# PSU2.net
KiCad netlist of a schematic drawn in Altium Designer
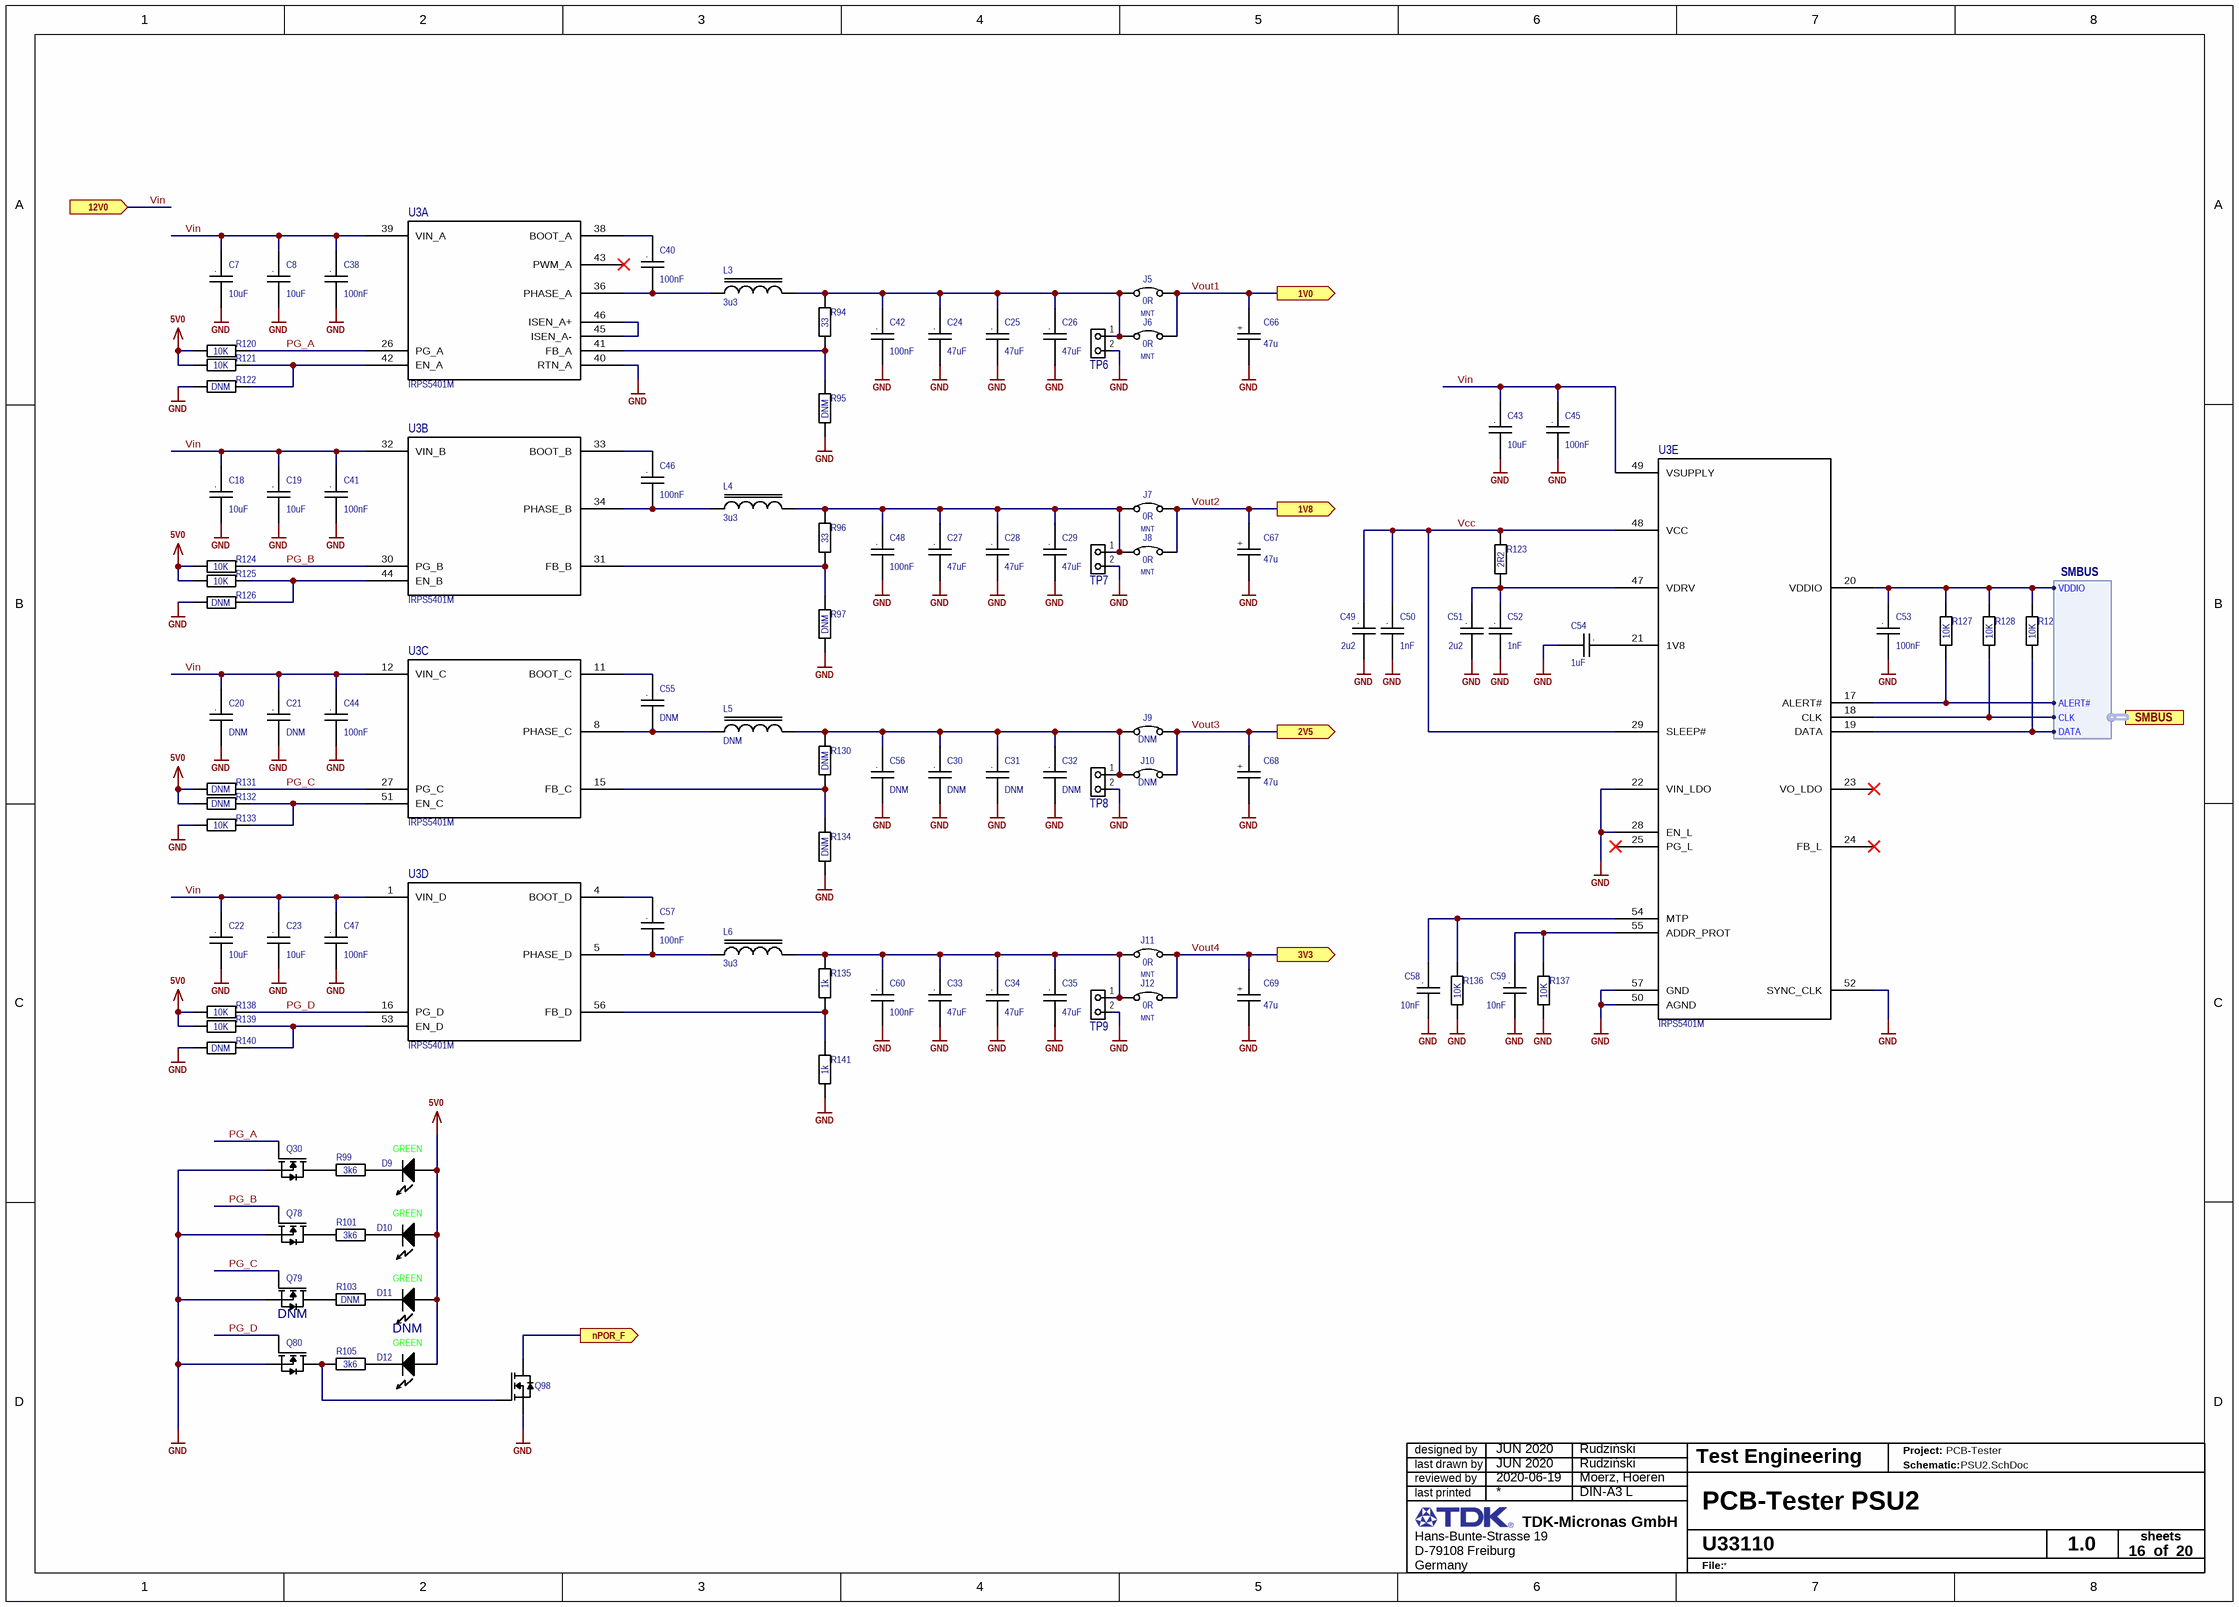
[diagram p0: PSU2.SchDoc]

(export (version "E")
  (design (tool "Eeschema 10.0.6"))
  (components
    (comp (ref "C7")
      (value "10uF")
      (footprint "C1206 Reflow")
      (description "CAP CER 10UF 25V X7R 1206")
      (fields
        (field (name "TOLERANCE") "±10%")
        (field (name "02. DISTRIBUTOR PART NUMBER") "445-7705-6-ND")
        (field (name "13. CREATED DATE/NAME") "AUG2018/Hören")
      )
      (libsource (lib "chickenfood") (part "C"))
    )
    (comp (ref "C8")
      (value "10uF")
      (footprint "C1206 Reflow")
      (description "CAP CER 10UF 25V X7R 1206")
      (fields
        (field (name "TOLERANCE") "±10%")
        (field (name "02. DISTRIBUTOR PART NUMBER") "445-7705-6-ND")
        (field (name "13. CREATED DATE/NAME") "AUG2018/Hören")
      )
      (libsource (lib "chickenfood") (part "C"))
    )
    (comp (ref "C18")
      (value "10uF")
      (footprint "C1206 Reflow")
      (description "CAP CER 10UF 25V X7R 1206")
      (fields
        (field (name "TOLERANCE") "±10%")
        (field (name "02. DISTRIBUTOR PART NUMBER") "445-7705-6-ND")
        (field (name "13. CREATED DATE/NAME") "AUG2018/Hören")
      )
      (libsource (lib "chickenfood") (part "C"))
    )
    (comp (ref "C19")
      (value "10uF")
      (footprint "C1206 Reflow")
      (description "CAP CER 10UF 25V X7R 1206")
      (fields
        (field (name "TOLERANCE") "±10%")
        (field (name "02. DISTRIBUTOR PART NUMBER") "445-7705-6-ND")
        (field (name "13. CREATED DATE/NAME") "AUG2018/Hören")
      )
      (libsource (lib "chickenfood") (part "C"))
    )
    (comp (ref "C20")
      (value "DNM")
      (footprint "C1206 Reflow")
      (description "CAP CER 10UF 25V X7R 1206")
      (fields
        (field (name "TOLERANCE") "±10%")
        (field (name "02. DISTRIBUTOR PART NUMBER") "445-7705-6-ND")
        (field (name "13. CREATED DATE/NAME") "AUG2018/Hören")
      )
      (libsource (lib "chickenfood") (part "C"))
    )
    (comp (ref "C21")
      (value "DNM")
      (footprint "C1206 Reflow")
      (description "CAP CER 10UF 25V X7R 1206")
      (fields
        (field (name "TOLERANCE") "±10%")
        (field (name "02. DISTRIBUTOR PART NUMBER") "445-7705-6-ND")
        (field (name "13. CREATED DATE/NAME") "AUG2018/Hören")
      )
      (libsource (lib "chickenfood") (part "C"))
    )
    (comp (ref "C22")
      (value "10uF")
      (footprint "C1206 Reflow")
      (description "CAP CER 10UF 25V X7R 1206")
      (fields
        (field (name "TOLERANCE") "±10%")
        (field (name "02. DISTRIBUTOR PART NUMBER") "445-7705-6-ND")
        (field (name "13. CREATED DATE/NAME") "AUG2018/Hören")
      )
      (libsource (lib "chickenfood") (part "C"))
    )
    (comp (ref "C23")
      (value "10uF")
      (footprint "C1206 Reflow")
      (description "CAP CER 10UF 25V X7R 1206")
      (fields
        (field (name "TOLERANCE") "±10%")
        (field (name "02. DISTRIBUTOR PART NUMBER") "445-7705-6-ND")
        (field (name "13. CREATED DATE/NAME") "AUG2018/Hören")
      )
      (libsource (lib "chickenfood") (part "C"))
    )
    (comp (ref "C24")
      (value "47uF")
      (footprint "C1210 Reflow")
      (description "CAP CER 47UF 10V X5R 1210")
      (fields
        (field (name "TOLERANCE") "±20%")
        (field (name "02. DISTRIBUTOR PART NUMBER") "1276-3380-6-ND")
        (field (name "13. CREATED DATE/NAME") "AUG2018/Hören")
      )
      (libsource (lib "chickenfood") (part "C"))
    )
    (comp (ref "C25")
      (value "47uF")
      (footprint "C1210 Reflow")
      (description "CAP CER 47UF 10V X5R 1210")
      (fields
        (field (name "TOLERANCE") "±20%")
        (field (name "02. DISTRIBUTOR PART NUMBER") "1276-3380-6-ND")
        (field (name "13. CREATED DATE/NAME") "AUG2018/Hören")
      )
      (libsource (lib "chickenfood") (part "C"))
    )
    (comp (ref "C26")
      (value "47uF")
      (footprint "C1210 Reflow")
      (description "CAP CER 47UF 10V X5R 1210")
      (fields
        (field (name "TOLERANCE") "±20%")
        (field (name "02. DISTRIBUTOR PART NUMBER") "1276-3380-6-ND")
        (field (name "13. CREATED DATE/NAME") "AUG2018/Hören")
      )
      (libsource (lib "chickenfood") (part "C"))
    )
    (comp (ref "C27")
      (value "47uF")
      (footprint "C1210 Reflow")
      (description "CAP CER 47UF 10V X5R 1210")
      (fields
        (field (name "TOLERANCE") "±20%")
        (field (name "02. DISTRIBUTOR PART NUMBER") "1276-3380-6-ND")
        (field (name "13. CREATED DATE/NAME") "AUG2018/Hören")
      )
      (libsource (lib "chickenfood") (part "C"))
    )
    (comp (ref "C28")
      (value "47uF")
      (footprint "C1210 Reflow")
      (description "CAP CER 47UF 10V X5R 1210")
      (fields
        (field (name "TOLERANCE") "±20%")
        (field (name "02. DISTRIBUTOR PART NUMBER") "1276-3380-6-ND")
        (field (name "13. CREATED DATE/NAME") "AUG2018/Hören")
      )
      (libsource (lib "chickenfood") (part "C"))
    )
    (comp (ref "C29")
      (value "47uF")
      (footprint "C1210 Reflow")
      (description "CAP CER 47UF 10V X5R 1210")
      (fields
        (field (name "TOLERANCE") "±20%")
        (field (name "02. DISTRIBUTOR PART NUMBER") "1276-3380-6-ND")
        (field (name "13. CREATED DATE/NAME") "AUG2018/Hören")
      )
      (libsource (lib "chickenfood") (part "C"))
    )
    (comp (ref "C30")
      (value "DNM")
      (footprint "C1210 Reflow")
      (description "CAP CER 47UF 10V X5R 1210")
      (fields
        (field (name "TOLERANCE") "±20%")
        (field (name "02. DISTRIBUTOR PART NUMBER") "1276-3380-6-ND")
        (field (name "13. CREATED DATE/NAME") "AUG2018/Hören")
      )
      (libsource (lib "chickenfood") (part "C"))
    )
    (comp (ref "C31")
      (value "DNM")
      (footprint "C1210 Reflow")
      (description "CAP CER 47UF 10V X5R 1210")
      (fields
        (field (name "TOLERANCE") "±20%")
        (field (name "02. DISTRIBUTOR PART NUMBER") "1276-3380-6-ND")
        (field (name "13. CREATED DATE/NAME") "AUG2018/Hören")
      )
      (libsource (lib "chickenfood") (part "C"))
    )
    (comp (ref "C32")
      (value "DNM")
      (footprint "C1210 Reflow")
      (description "CAP CER 47UF 10V X5R 1210")
      (fields
        (field (name "TOLERANCE") "±20%")
        (field (name "02. DISTRIBUTOR PART NUMBER") "1276-3380-6-ND")
        (field (name "13. CREATED DATE/NAME") "AUG2018/Hören")
      )
      (libsource (lib "chickenfood") (part "C"))
    )
    (comp (ref "C33")
      (value "47uF")
      (footprint "C1210 Reflow")
      (description "CAP CER 47UF 10V X5R 1210")
      (fields
        (field (name "TOLERANCE") "±20%")
        (field (name "02. DISTRIBUTOR PART NUMBER") "1276-3380-6-ND")
        (field (name "13. CREATED DATE/NAME") "AUG2018/Hören")
      )
      (libsource (lib "chickenfood") (part "C"))
    )
    (comp (ref "C34")
      (value "47uF")
      (footprint "C1210 Reflow")
      (description "CAP CER 47UF 10V X5R 1210")
      (fields
        (field (name "TOLERANCE") "±20%")
        (field (name "02. DISTRIBUTOR PART NUMBER") "1276-3380-6-ND")
        (field (name "13. CREATED DATE/NAME") "AUG2018/Hören")
      )
      (libsource (lib "chickenfood") (part "C"))
    )
    (comp (ref "C35")
      (value "47uF")
      (footprint "C1210 Reflow")
      (description "CAP CER 47UF 10V X5R 1210")
      (fields
        (field (name "TOLERANCE") "±20%")
        (field (name "02. DISTRIBUTOR PART NUMBER") "1276-3380-6-ND")
        (field (name "13. CREATED DATE/NAME") "AUG2018/Hören")
      )
      (libsource (lib "chickenfood") (part "C"))
    )
    (comp (ref "C38")
      (value "100nF")
      (footprint "C0402 Reflow")
      (description "CAP CER 0.1UF 25V X7R 0402")
      (fields
        (field (name "TOLERANCE") "±10%")
        (field (name "02. DISTRIBUTOR PART NUMBER") "311-2077-6-ND")
        (field (name "13. CREATED DATE/NAME") "AUG2018/Hören")
      )
      (libsource (lib "chickenfood") (part "C"))
    )
    (comp (ref "C40")
      (value "100nF")
      (footprint "C0402 Reflow")
      (description "CAP CER 0.1UF 25V X7R 0402")
      (fields
        (field (name "TOLERANCE") "±10%")
        (field (name "02. DISTRIBUTOR PART NUMBER") "311-2077-6-ND")
        (field (name "13. CREATED DATE/NAME") "AUG2018/Hören")
      )
      (libsource (lib "chickenfood") (part "C"))
    )
    (comp (ref "C41")
      (value "100nF")
      (footprint "C0402 Reflow")
      (description "CAP CER 0.1UF 25V X7R 0402")
      (fields
        (field (name "TOLERANCE") "±10%")
        (field (name "02. DISTRIBUTOR PART NUMBER") "311-2077-6-ND")
        (field (name "13. CREATED DATE/NAME") "AUG2018/Hören")
      )
      (libsource (lib "chickenfood") (part "C"))
    )
    (comp (ref "C42")
      (value "100nF")
      (footprint "C0402 Reflow")
      (description "CAP CER 0.1UF 25V X7R 0402")
      (fields
        (field (name "TOLERANCE") "±10%")
        (field (name "02. DISTRIBUTOR PART NUMBER") "311-2077-6-ND")
        (field (name "13. CREATED DATE/NAME") "AUG2018/Hören")
      )
      (libsource (lib "chickenfood") (part "C"))
    )
    (comp (ref "C43")
      (value "10uF")
      (footprint "C1206 Reflow")
      (description "CAP CER 10UF 25V X7R 1206")
      (fields
        (field (name "TOLERANCE") "±10%")
        (field (name "02. DISTRIBUTOR PART NUMBER") "445-7705-6-ND")
        (field (name "13. CREATED DATE/NAME") "AUG2018/Hören")
      )
      (libsource (lib "chickenfood") (part "C"))
    )
    (comp (ref "C44")
      (value "100nF")
      (footprint "C0402 Reflow")
      (description "CAP CER 0.1UF 25V X7R 0402")
      (fields
        (field (name "TOLERANCE") "±10%")
        (field (name "02. DISTRIBUTOR PART NUMBER") "311-2077-6-ND")
        (field (name "13. CREATED DATE/NAME") "AUG2018/Hören")
      )
      (libsource (lib "chickenfood") (part "C"))
    )
    (comp (ref "C45")
      (value "100nF")
      (footprint "C0402 Reflow")
      (description "CAP CER 0.1UF 25V X7R 0402")
      (fields
        (field (name "TOLERANCE") "±10%")
        (field (name "02. DISTRIBUTOR PART NUMBER") "311-2077-6-ND")
        (field (name "13. CREATED DATE/NAME") "AUG2018/Hören")
      )
      (libsource (lib "chickenfood") (part "C"))
    )
    (comp (ref "C46")
      (value "100nF")
      (footprint "C0402 Reflow")
      (description "CAP CER 0.1UF 25V X7R 0402")
      (fields
        (field (name "TOLERANCE") "±10%")
        (field (name "02. DISTRIBUTOR PART NUMBER") "311-2077-6-ND")
        (field (name "13. CREATED DATE/NAME") "AUG2018/Hören")
      )
      (libsource (lib "chickenfood") (part "C"))
    )
    (comp (ref "C47")
      (value "100nF")
      (footprint "C0402 Reflow")
      (description "CAP CER 0.1UF 25V X7R 0402")
      (fields
        (field (name "TOLERANCE") "±10%")
        (field (name "02. DISTRIBUTOR PART NUMBER") "311-2077-6-ND")
        (field (name "13. CREATED DATE/NAME") "AUG2018/Hören")
      )
      (libsource (lib "chickenfood") (part "C"))
    )
    (comp (ref "C48")
      (value "100nF")
      (footprint "C0402 Reflow")
      (description "CAP CER 0.1UF 25V X7R 0402")
      (fields
        (field (name "TOLERANCE") "±10%")
        (field (name "02. DISTRIBUTOR PART NUMBER") "311-2077-6-ND")
        (field (name "13. CREATED DATE/NAME") "AUG2018/Hören")
      )
      (libsource (lib "chickenfood") (part "C"))
    )
    (comp (ref "C49")
      (value "2u2")
      (footprint "C0805 Reflow")
      (description "CAP CER 2.2UF 10V X7R 0805")
      (fields
        (field (name "02. DISTRIBUTOR PART NUMBER") "1276-1188-1-ND")
        (field (name "07. MANUFACTURER  PART NUMBER") "CL21B225KPFNNNE")
      )
      (libsource (lib "PCB-Tester-Board-V1") (part "C_11"))
    )
    (comp (ref "C50")
      (value "1nF")
      (footprint "C0402 Reflow")
      (description "CAP CER 1000PF 25V X7R 0402")
      (fields
        (field (name "TOLERANCE") "±10%")
        (field (name "02. DISTRIBUTOR PART NUMBER") "399-1031-6-ND")
        (field (name "13. CREATED DATE/NAME") "AUG2018/Hören")
      )
      (libsource (lib "PCB-Tester-Board-V1") (part "C_7"))
    )
    (comp (ref "C51")
      (value "2u2")
      (footprint "C0805 Reflow")
      (description "CAP CER 2.2UF 10V X7R 0805")
      (fields
        (field (name "02. DISTRIBUTOR PART NUMBER") "1276-1188-1-ND")
        (field (name "07. MANUFACTURER  PART NUMBER") "CL21B225KPFNNNE")
      )
      (libsource (lib "PCB-Tester-Board-V1") (part "C_11"))
    )
    (comp (ref "C52")
      (value "1nF")
      (footprint "C0402 Reflow")
      (description "CAP CER 1000PF 25V X7R 0402")
      (fields
        (field (name "TOLERANCE") "±10%")
        (field (name "02. DISTRIBUTOR PART NUMBER") "399-1031-6-ND")
        (field (name "13. CREATED DATE/NAME") "AUG2018/Hören")
      )
      (libsource (lib "PCB-Tester-Board-V1") (part "C_7"))
    )
    (comp (ref "C53")
      (value "100nF")
      (footprint "C0402 Reflow")
      (description "CAP CER 0.1UF 25V X7R 0402")
      (fields
        (field (name "TOLERANCE") "±10%")
        (field (name "02. DISTRIBUTOR PART NUMBER") "311-2077-6-ND")
        (field (name "13. CREATED DATE/NAME") "AUG2018/Hören")
      )
      (libsource (lib "chickenfood") (part "C"))
    )
    (comp (ref "C54")
      (value "1uF")
      (footprint "C0402 Reflow")
      (description "CAP CER 1UF 6.3V X7R 0402")
      (fields
        (field (name "TOLERANCE") "±10%")
        (field (name "02. DISTRIBUTOR PART NUMBER") "490-13339-6-ND")
        (field (name "13. CREATED DATE/NAME") "AUG2018/Hören")
      )
      (libsource (lib "PCB-Tester-Board-V1") (part "C_2"))
    )
    (comp (ref "C55")
      (value "DNM")
      (footprint "C0402 Reflow")
      (description "CAP CER 0.1UF 25V X7R 0402")
      (fields
        (field (name "TOLERANCE") "±10%")
        (field (name "02. DISTRIBUTOR PART NUMBER") "311-2077-6-ND")
        (field (name "13. CREATED DATE/NAME") "AUG2018/Hören")
      )
      (libsource (lib "chickenfood") (part "C"))
    )
    (comp (ref "C56")
      (value "DNM")
      (footprint "C0402 Reflow")
      (description "CAP CER 0.1UF 25V X7R 0402")
      (fields
        (field (name "TOLERANCE") "±10%")
        (field (name "02. DISTRIBUTOR PART NUMBER") "311-2077-6-ND")
        (field (name "13. CREATED DATE/NAME") "AUG2018/Hören")
      )
      (libsource (lib "chickenfood") (part "C"))
    )
    (comp (ref "C57")
      (value "100nF")
      (footprint "C0402 Reflow")
      (description "CAP CER 0.1UF 25V X7R 0402")
      (fields
        (field (name "TOLERANCE") "±10%")
        (field (name "02. DISTRIBUTOR PART NUMBER") "311-2077-6-ND")
        (field (name "13. CREATED DATE/NAME") "AUG2018/Hören")
      )
      (libsource (lib "chickenfood") (part "C"))
    )
    (comp (ref "C58")
      (value "10nF")
      (footprint "C0402 Reflow")
      (description "CAP CER 0.01UF 25V X7R 0402")
      (fields (field (name "TOLERANCE") "±10%") (field (name "02. DISTRIBUTOR PART NUMBER") "490-6043-1-ND"))
      (libsource (lib "PCB-Tester-Board-V1") (part "C_10"))
    )
    (comp (ref "C59")
      (value "10nF")
      (footprint "C0402 Reflow")
      (description "CAP CER 0.01UF 25V X7R 0402")
      (fields (field (name "TOLERANCE") "±10%") (field (name "02. DISTRIBUTOR PART NUMBER") "490-6043-1-ND"))
      (libsource (lib "PCB-Tester-Board-V1") (part "C_10"))
    )
    (comp (ref "C60")
      (value "100nF")
      (footprint "C0402 Reflow")
      (description "CAP CER 0.1UF 25V X7R 0402")
      (fields
        (field (name "TOLERANCE") "±10%")
        (field (name "02. DISTRIBUTOR PART NUMBER") "311-2077-6-ND")
        (field (name "13. CREATED DATE/NAME") "AUG2018/Hören")
      )
      (libsource (lib "chickenfood") (part "C"))
    )
    (comp (ref "C66")
      (value "47u")
      (footprint "CAP_TAN_B")
      (description "CAP TANT 47UF 20% 10V 1411")
      (fields
        (field (name "02. DISTRIBUTOR PART NUMBER") "478-12531-1-ND")
        (field (name "07. MANUFACTURER  PART NUMBER") "F971A476MBAHT3")
      )
      (libsource (lib "PCB-Tester-Board-V1") (part "C+_TAN"))
    )
    (comp (ref "C67")
      (value "47u")
      (footprint "CAP_TAN_B")
      (description "CAP TANT 47UF 20% 10V 1411")
      (fields
        (field (name "02. DISTRIBUTOR PART NUMBER") "478-12531-1-ND")
        (field (name "07. MANUFACTURER  PART NUMBER") "F971A476MBAHT3")
      )
      (libsource (lib "PCB-Tester-Board-V1") (part "C+_TAN"))
    )
    (comp (ref "C68")
      (value "47u")
      (footprint "CAP_TAN_B")
      (description "CAP TANT 47UF 20% 10V 1411")
      (fields
        (field (name "02. DISTRIBUTOR PART NUMBER") "478-12531-1-ND")
        (field (name "07. MANUFACTURER  PART NUMBER") "F971A476MBAHT3")
      )
      (libsource (lib "PCB-Tester-Board-V1") (part "C+_TAN"))
    )
    (comp (ref "C69")
      (value "47u")
      (footprint "CAP_TAN_B")
      (description "CAP TANT 47UF 20% 10V 1411")
      (fields
        (field (name "02. DISTRIBUTOR PART NUMBER") "478-12531-1-ND")
        (field (name "07. MANUFACTURER  PART NUMBER") "F971A476MBAHT3")
      )
      (libsource (lib "PCB-Tester-Board-V1") (part "C+_TAN"))
    )
    (comp (ref "D9")
      (value "D")
      (footprint "L0603G")
      (description "LED GREEN DIFFUSED 0603 SMD")
      (fields
        (field (name "02. DISTRIBUTOR PART NUMBER") "475-2709-6-ND")
        (field (name "07. MANUFACTURER  PART NUMBER") "LG L29K-G2J1-24-Z")
        (field (name "COLOR") "GREEN")
        (field (name "13. CREATED DATE/NAME") "AUG2018/Hören")
      )
      (libsource (lib "chickenfood") (part "LED"))
    )
    (comp (ref "D10")
      (value "D")
      (footprint "L0603G")
      (description "LED GREEN DIFFUSED 0603 SMD")
      (fields
        (field (name "02. DISTRIBUTOR PART NUMBER") "475-2709-6-ND")
        (field (name "07. MANUFACTURER  PART NUMBER") "LG L29K-G2J1-24-Z")
        (field (name "COLOR") "GREEN")
        (field (name "13. CREATED DATE/NAME") "AUG2018/Hören")
      )
      (libsource (lib "chickenfood") (part "LED"))
    )
    (comp (ref "D11")
      (value "D")
      (footprint "L0603G")
      (description "LED GREEN DIFFUSED 0603 SMD")
      (fields
        (field (name "02. DISTRIBUTOR PART NUMBER") "475-2709-6-ND")
        (field (name "07. MANUFACTURER  PART NUMBER") "LG L29K-G2J1-24-Z")
        (field (name "COLOR") "GREEN")
        (field (name "NICNAME") "DNM")
        (field (name "13. CREATED DATE/NAME") "AUG2018/Hören")
      )
      (libsource (lib "chickenfood") (part "LED"))
    )
    (comp (ref "D12")
      (value "D")
      (footprint "L0603G")
      (description "LED GREEN DIFFUSED 0603 SMD")
      (fields
        (field (name "02. DISTRIBUTOR PART NUMBER") "475-2709-6-ND")
        (field (name "07. MANUFACTURER  PART NUMBER") "LG L29K-G2J1-24-Z")
        (field (name "COLOR") "GREEN")
        (field (name "13. CREATED DATE/NAME") "AUG2018/Hören")
      )
      (libsource (lib "chickenfood") (part "LED"))
    )
    (comp (ref "J5")
      (value "0R")
      (footprint "JumperSMD")
      (description "RES SMD 0 OHM JUMPER 1/10W 0603")
      (fields
        (field (name "02. DISTRIBUTOR PART NUMBER") "311-0.0GRDKR-ND")
        (field (name "07. MANUFACTURER  PART NUMBER") "RC0603JR-070RL")
        (field (name "POPULATED") "MNT")
      )
      (libsource (lib "chickenfood") (part "Jumper SMD"))
    )
    (comp (ref "J6")
      (value "0R")
      (footprint "JumperSMD")
      (description "RES SMD 0 OHM JUMPER 1/10W 0603")
      (fields
        (field (name "02. DISTRIBUTOR PART NUMBER") "311-0.0GRDKR-ND")
        (field (name "07. MANUFACTURER  PART NUMBER") "RC0603JR-070RL")
        (field (name "POPULATED") "MNT")
      )
      (libsource (lib "chickenfood") (part "Jumper SMD"))
    )
    (comp (ref "J7")
      (value "0R")
      (footprint "JumperSMD")
      (description "RES SMD 0 OHM JUMPER 1/10W 0603")
      (fields
        (field (name "02. DISTRIBUTOR PART NUMBER") "311-0.0GRDKR-ND")
        (field (name "07. MANUFACTURER  PART NUMBER") "RC0603JR-070RL")
        (field (name "POPULATED") "MNT")
      )
      (libsource (lib "chickenfood") (part "Jumper SMD"))
    )
    (comp (ref "J8")
      (value "0R")
      (footprint "JumperSMD")
      (description "RES SMD 0 OHM JUMPER 1/10W 0603")
      (fields
        (field (name "02. DISTRIBUTOR PART NUMBER") "311-0.0GRDKR-ND")
        (field (name "07. MANUFACTURER  PART NUMBER") "RC0603JR-070RL")
        (field (name "POPULATED") "MNT")
      )
      (libsource (lib "chickenfood") (part "Jumper SMD"))
    )
    (comp (ref "J9")
      (value "DNM")
      (footprint "JumperSMD")
      (description "RES SMD 0 OHM JUMPER 1/10W 0603")
      (fields
        (field (name "02. DISTRIBUTOR PART NUMBER") "311-0.0GRDKR-ND")
        (field (name "07. MANUFACTURER  PART NUMBER") "RC0603JR-070RL")
      )
      (libsource (lib "chickenfood") (part "Jumper SMD"))
    )
    (comp (ref "J10")
      (value "DNM")
      (footprint "JumperSMD")
      (description "RES SMD 0 OHM JUMPER 1/10W 0603")
      (fields
        (field (name "02. DISTRIBUTOR PART NUMBER") "311-0.0GRDKR-ND")
        (field (name "07. MANUFACTURER  PART NUMBER") "RC0603JR-070RL")
      )
      (libsource (lib "chickenfood") (part "Jumper SMD"))
    )
    (comp (ref "J11")
      (value "0R")
      (footprint "JumperSMD")
      (description "RES SMD 0 OHM JUMPER 1/10W 0603")
      (fields
        (field (name "02. DISTRIBUTOR PART NUMBER") "311-0.0GRDKR-ND")
        (field (name "07. MANUFACTURER  PART NUMBER") "RC0603JR-070RL")
        (field (name "POPULATED") "MNT")
      )
      (libsource (lib "chickenfood") (part "Jumper SMD"))
    )
    (comp (ref "J12")
      (value "0R")
      (footprint "JumperSMD")
      (description "RES SMD 0 OHM JUMPER 1/10W 0603")
      (fields
        (field (name "02. DISTRIBUTOR PART NUMBER") "311-0.0GRDKR-ND")
        (field (name "07. MANUFACTURER  PART NUMBER") "RC0603JR-070RL")
        (field (name "POPULATED") "MNT")
      )
      (libsource (lib "chickenfood") (part "Jumper SMD"))
    )
    (comp (ref "L3")
      (value "L")
      (footprint "XAL7070")
      (description "Fixed Inductors 3.3uH Shld 20% 15.1A 9.42mOhms AECQ2")
      (fields
        (field (name "02. DISTRIBUTOR PART NUMBER") "994-XAL7070-332MEC")
        (field (name "07. MANUFACTURER  PART NUMBER") "XAL7070-332MEC")
        (field (name "INDUCTANCE") "3u3")
      )
      (libsource (lib "PCB-Tester-Board-V1") (part "INDUCTOR"))
    )
    (comp (ref "L4")
      (value "L")
      (footprint "XAL7070")
      (description "Fixed Inductors 3.3uH Shld 20% 15.1A 9.42mOhms AECQ2")
      (fields
        (field (name "02. DISTRIBUTOR PART NUMBER") "994-XAL7070-332MEC")
        (field (name "07. MANUFACTURER  PART NUMBER") "XAL7070-332MEC")
        (field (name "INDUCTANCE") "3u3")
      )
      (libsource (lib "PCB-Tester-Board-V1") (part "INDUCTOR"))
    )
    (comp (ref "L5")
      (value "L")
      (footprint "XAL7070")
      (description "Fixed Inductors 3.3uH Shld 20% 15.1A 9.42mOhms AECQ2")
      (fields
        (field (name "02. DISTRIBUTOR PART NUMBER") "994-XAL7070-332MEC")
        (field (name "07. MANUFACTURER  PART NUMBER") "XAL7070-332MEC")
        (field (name "INDUCTANCE") "DNM")
      )
      (libsource (lib "PCB-Tester-Board-V1") (part "INDUCTOR"))
    )
    (comp (ref "L6")
      (value "L")
      (footprint "XAL7070")
      (description "Fixed Inductors 3.3uH Shld 20% 15.1A 9.42mOhms AECQ2")
      (fields
        (field (name "02. DISTRIBUTOR PART NUMBER") "994-XAL7070-332MEC")
        (field (name "07. MANUFACTURER  PART NUMBER") "XAL7070-332MEC")
        (field (name "INDUCTANCE") "3u3")
      )
      (libsource (lib "PCB-Tester-Board-V1") (part "INDUCTOR"))
    )
    (comp (ref "Q30")
      (value "Q")
      (footprint "SOT23-3")
      (description "MOSFET N-CH 25V 680MA SOT-23")
      (fields
        (field (name "02. DISTRIBUTOR PART NUMBER") "FDV303NDKR-ND")
        (field (name "07. MANUFACTURER  PART NUMBER") "FDV303N")
        (field (name "13. CREATED DATE/NAME") "AUG 2018 / Hören")
      )
      (libsource (lib "PCB-Tester-Board-V1") (part "FDV303N"))
    )
    (comp (ref "Q78")
      (value "Q")
      (footprint "SOT23-3")
      (description "MOSFET N-CH 25V 680MA SOT-23")
      (fields
        (field (name "02. DISTRIBUTOR PART NUMBER") "FDV303NDKR-ND")
        (field (name "07. MANUFACTURER  PART NUMBER") "FDV303N")
        (field (name "13. CREATED DATE/NAME") "AUG 2018 / Hören")
      )
      (libsource (lib "PCB-Tester-Board-V1") (part "FDV303N"))
    )
    (comp (ref "Q79")
      (value "Q")
      (footprint "SOT23-3")
      (description "MOSFET N-CH 25V 680MA SOT-23")
      (fields
        (field (name "02. DISTRIBUTOR PART NUMBER") "FDV303NDKR-ND")
        (field (name "07. MANUFACTURER  PART NUMBER") "FDV303N")
        (field (name "NICNAME") "DNM")
        (field (name "13. CREATED DATE/NAME") "AUG 2018 / Hören")
      )
      (libsource (lib "PCB-Tester-Board-V1") (part "FDV303N"))
    )
    (comp (ref "Q80")
      (value "Q")
      (footprint "SOT23-3")
      (description "MOSFET N-CH 25V 680MA SOT-23")
      (fields
        (field (name "02. DISTRIBUTOR PART NUMBER") "FDV303NDKR-ND")
        (field (name "07. MANUFACTURER  PART NUMBER") "FDV303N")
        (field (name "13. CREATED DATE/NAME") "AUG 2018 / Hören")
      )
      (libsource (lib "PCB-Tester-Board-V1") (part "FDV303N"))
    )
    (comp (ref "Q98")
      (value "Q")
      (footprint "SOT23-3")
      (description "MOSFET N-CH 25V 680MA SOT-23")
      (fields
        (field (name "02. DISTRIBUTOR PART NUMBER") "FDV303NDKR-ND")
        (field (name "07. MANUFACTURER  PART NUMBER") "FDV303N")
        (field (name "13. CREATED DATE/NAME") "AUG 2018 / Hören")
      )
      (libsource (lib "PCB-Tester-Board-V1") (part "FDV303N"))
    )
    (comp (ref "R94")
      (value "33")
      (footprint "R0402 Reflow")
      (description "RES SMD 33 OHM 1% 1/16W 0402")
      (fields
        (field (name "TOLERANCE") "±1%")
        (field (name "02. DISTRIBUTOR PART NUMBER") "311-33.0LRDKR-ND")
        (field (name "13. CREATED DATE/NAME") "AUG2018/Hören")
      )
      (libsource (lib "") (part "R_1"))
    )
    (comp (ref "R95")
      (value "DNM")
      (footprint "R0402 Reflow")
      (description "RES SMD 10K OHM 1% 1/16W 0402")
      (fields
        (field (name "TOLERANCE") "±1%")
        (field (name "02. DISTRIBUTOR PART NUMBER") "311-10.0KLRDKR-ND")
        (field (name "13. CREATED DATE/NAME") "AUG2018/Hören")
      )
      (libsource (lib "") (part "R_1"))
    )
    (comp (ref "R96")
      (value "33")
      (footprint "R0402 Reflow")
      (description "RES SMD 33 OHM 1% 1/16W 0402")
      (fields
        (field (name "TOLERANCE") "±1%")
        (field (name "02. DISTRIBUTOR PART NUMBER") "311-33.0LRDKR-ND")
        (field (name "13. CREATED DATE/NAME") "AUG2018/Hören")
      )
      (libsource (lib "") (part "R_1"))
    )
    (comp (ref "R97")
      (value "DNM")
      (footprint "R0402 Reflow")
      (description "RES SMD 10K OHM 1% 1/16W 0402")
      (fields
        (field (name "TOLERANCE") "±1%")
        (field (name "02. DISTRIBUTOR PART NUMBER") "311-10.0KLRDKR-ND")
        (field (name "13. CREATED DATE/NAME") "AUG2018/Hören")
      )
      (libsource (lib "") (part "R_1"))
    )
    (comp (ref "R99")
      (value "3k6")
      (footprint "R0603 Reflow")
      (description "RES SMD 3.6K OHM 1% 1/10W 0603")
      (fields
        (field (name "TOLERANCE") "±1%")
        (field (name "02. DISTRIBUTOR PART NUMBER") "311-3.60KHRCT-ND")
        (field (name "13. CREATED DATE/NAME") "AUG2018/Hören")
      )
      (libsource (lib "") (part "R_2"))
    )
    (comp (ref "R101")
      (value "3k6")
      (footprint "R0603 Reflow")
      (description "RES SMD 3.6K OHM 1% 1/10W 0603")
      (fields
        (field (name "TOLERANCE") "±1%")
        (field (name "02. DISTRIBUTOR PART NUMBER") "311-3.60KHRCT-ND")
        (field (name "13. CREATED DATE/NAME") "AUG2018/Hören")
      )
      (libsource (lib "") (part "R_2"))
    )
    (comp (ref "R103")
      (value "DNM")
      (footprint "R0603 Reflow")
      (description "RES SMD 1.65K OHM 1% 1/16W 0402")
      (fields
        (field (name "TOLERANCE") "±1%")
        (field (name "02. DISTRIBUTOR PART NUMBER") "YAG3043DKR-ND")
        (field (name "13. CREATED DATE/NAME") "AUG2018/Hören")
      )
      (libsource (lib "") (part "R_2"))
    )
    (comp (ref "R105")
      (value "3k6")
      (footprint "R0603 Reflow")
      (description "RES SMD 3.6K OHM 1% 1/10W 0603")
      (fields
        (field (name "TOLERANCE") "±1%")
        (field (name "02. DISTRIBUTOR PART NUMBER") "311-3.60KHRCT-ND")
        (field (name "13. CREATED DATE/NAME") "AUG2018/Hören")
      )
      (libsource (lib "") (part "R_2"))
    )
    (comp (ref "R120")
      (value "10K")
      (footprint "R0402 Reflow")
      (description "RES SMD 10K OHM 1% 1/16W 0402")
      (fields
        (field (name "TOLERANCE") "±1%")
        (field (name "02. DISTRIBUTOR PART NUMBER") "311-10.0KLRDKR-ND")
        (field (name "13. CREATED DATE/NAME") "AUG2018/Hören")
      )
      (libsource (lib "chickenfood") (part "R"))
    )
    (comp (ref "R121")
      (value "10K")
      (footprint "R0402 Reflow")
      (description "RES SMD 10K OHM 1% 1/16W 0402")
      (fields
        (field (name "TOLERANCE") "±1%")
        (field (name "02. DISTRIBUTOR PART NUMBER") "311-10.0KLRDKR-ND")
        (field (name "13. CREATED DATE/NAME") "AUG2018/Hören")
      )
      (libsource (lib "chickenfood") (part "R"))
    )
    (comp (ref "R122")
      (value "DNM")
      (footprint "R0402 Reflow")
      (description "RES SMD 10K OHM 1% 1/16W 0402")
      (fields
        (field (name "TOLERANCE") "±1%")
        (field (name "02. DISTRIBUTOR PART NUMBER") "311-10.0KLRDKR-ND")
        (field (name "13. CREATED DATE/NAME") "AUG2018/Hören")
      )
      (libsource (lib "chickenfood") (part "R"))
    )
    (comp (ref "R123")
      (value "2R2")
      (footprint "R0402 Reflow")
      (description "RES SMD 2.2 OHM 1% 1/16W 0402")
      (fields (field (name "TOLERANCE") "±1%") (field (name "02. DISTRIBUTOR PART NUMBER") "311-2.20LRTR-ND"))
      (libsource (lib "PCB-Tester-Board-V1") (part "R_24"))
    )
    (comp (ref "R124")
      (value "10K")
      (footprint "R0402 Reflow")
      (description "RES SMD 10K OHM 1% 1/16W 0402")
      (fields
        (field (name "TOLERANCE") "±1%")
        (field (name "02. DISTRIBUTOR PART NUMBER") "311-10.0KLRDKR-ND")
        (field (name "13. CREATED DATE/NAME") "AUG2018/Hören")
      )
      (libsource (lib "chickenfood") (part "R"))
    )
    (comp (ref "R125")
      (value "10K")
      (footprint "R0402 Reflow")
      (description "RES SMD 10K OHM 1% 1/16W 0402")
      (fields
        (field (name "TOLERANCE") "±1%")
        (field (name "02. DISTRIBUTOR PART NUMBER") "311-10.0KLRDKR-ND")
        (field (name "13. CREATED DATE/NAME") "AUG2018/Hören")
      )
      (libsource (lib "chickenfood") (part "R"))
    )
    (comp (ref "R126")
      (value "DNM")
      (footprint "R0402 Reflow")
      (description "RES SMD 10K OHM 1% 1/16W 0402")
      (fields
        (field (name "TOLERANCE") "±1%")
        (field (name "02. DISTRIBUTOR PART NUMBER") "311-10.0KLRDKR-ND")
        (field (name "13. CREATED DATE/NAME") "AUG2018/Hören")
      )
      (libsource (lib "chickenfood") (part "R"))
    )
    (comp (ref "R127")
      (value "10K")
      (footprint "R0402 Reflow")
      (description "RES SMD 10K OHM 1% 1/16W 0402")
      (fields
        (field (name "TOLERANCE") "±1%")
        (field (name "02. DISTRIBUTOR PART NUMBER") "311-10.0KLRDKR-ND")
        (field (name "13. CREATED DATE/NAME") "AUG2018/Hören")
      )
      (libsource (lib "") (part "R_1"))
    )
    (comp (ref "R128")
      (value "10K")
      (footprint "R0402 Reflow")
      (description "RES SMD 10K OHM 1% 1/16W 0402")
      (fields
        (field (name "TOLERANCE") "±1%")
        (field (name "02. DISTRIBUTOR PART NUMBER") "311-10.0KLRDKR-ND")
        (field (name "13. CREATED DATE/NAME") "AUG2018/Hören")
      )
      (libsource (lib "") (part "R_1"))
    )
    (comp (ref "R129")
      (value "10K")
      (footprint "R0402 Reflow")
      (description "RES SMD 10K OHM 1% 1/16W 0402")
      (fields
        (field (name "TOLERANCE") "±1%")
        (field (name "02. DISTRIBUTOR PART NUMBER") "311-10.0KLRDKR-ND")
        (field (name "13. CREATED DATE/NAME") "AUG2018/Hören")
      )
      (libsource (lib "") (part "R_1"))
    )
    (comp (ref "R130")
      (value "DNM")
      (footprint "R0402 Reflow")
      (description "RES SMD 10K OHM 1% 1/16W 0402")
      (fields
        (field (name "TOLERANCE") "±1%")
        (field (name "02. DISTRIBUTOR PART NUMBER") "311-10.0KLRDKR-ND")
        (field (name "13. CREATED DATE/NAME") "AUG2018/Hören")
      )
      (libsource (lib "") (part "R_1"))
    )
    (comp (ref "R131")
      (value "DNM")
      (footprint "R0402 Reflow")
      (description "RES SMD 10K OHM 1% 1/16W 0402")
      (fields
        (field (name "TOLERANCE") "±1%")
        (field (name "02. DISTRIBUTOR PART NUMBER") "311-10.0KLRDKR-ND")
        (field (name "13. CREATED DATE/NAME") "AUG2018/Hören")
      )
      (libsource (lib "chickenfood") (part "R"))
    )
    (comp (ref "R132")
      (value "DNM")
      (footprint "R0402 Reflow")
      (description "RES SMD 10K OHM 1% 1/16W 0402")
      (fields
        (field (name "TOLERANCE") "±1%")
        (field (name "02. DISTRIBUTOR PART NUMBER") "311-10.0KLRDKR-ND")
        (field (name "13. CREATED DATE/NAME") "AUG2018/Hören")
      )
      (libsource (lib "chickenfood") (part "R"))
    )
    (comp (ref "R133")
      (value "10K")
      (footprint "R0402 Reflow")
      (description "RES SMD 10K OHM 1% 1/16W 0402")
      (fields
        (field (name "TOLERANCE") "±1%")
        (field (name "02. DISTRIBUTOR PART NUMBER") "311-10.0KLRDKR-ND")
        (field (name "13. CREATED DATE/NAME") "AUG2018/Hören")
      )
      (libsource (lib "chickenfood") (part "R"))
    )
    (comp (ref "R134")
      (value "DNM")
      (footprint "R0402 Reflow")
      (description "RES SMD 10K OHM 1% 1/16W 0402")
      (fields
        (field (name "TOLERANCE") "±1%")
        (field (name "02. DISTRIBUTOR PART NUMBER") "311-10.0KLRDKR-ND")
        (field (name "13. CREATED DATE/NAME") "AUG2018/Hören")
      )
      (libsource (lib "") (part "R_1"))
    )
    (comp (ref "R135")
      (value "1k")
      (footprint "R0402 Reflow")
      (description "RES SMD 1K OHM 1% 1/16W 0402")
      (fields
        (field (name "TOLERANCE") "±1%")
        (field (name "02. DISTRIBUTOR PART NUMBER") "YAG1254CT-ND")
        (field (name "13. CREATED DATE/NAME") "AUG2018/Hören")
      )
      (libsource (lib "") (part "R_1"))
    )
    (comp (ref "R136")
      (value "10K")
      (footprint "R0402 Reflow")
      (description "RES SMD 10K OHM 1% 1/16W 0402")
      (fields
        (field (name "TOLERANCE") "±1%")
        (field (name "02. DISTRIBUTOR PART NUMBER") "311-10.0KLRDKR-ND")
        (field (name "13. CREATED DATE/NAME") "AUG2018/Hören")
      )
      (libsource (lib "") (part "R_1"))
    )
    (comp (ref "R137")
      (value "10K")
      (footprint "R0402 Reflow")
      (description "RES SMD 10K OHM 1% 1/16W 0402")
      (fields
        (field (name "TOLERANCE") "±1%")
        (field (name "02. DISTRIBUTOR PART NUMBER") "311-10.0KLRDKR-ND")
        (field (name "13. CREATED DATE/NAME") "AUG2018/Hören")
      )
      (libsource (lib "") (part "R_1"))
    )
    (comp (ref "R138")
      (value "10K")
      (footprint "R0402 Reflow")
      (description "RES SMD 10K OHM 1% 1/16W 0402")
      (fields
        (field (name "TOLERANCE") "±1%")
        (field (name "02. DISTRIBUTOR PART NUMBER") "311-10.0KLRDKR-ND")
        (field (name "13. CREATED DATE/NAME") "AUG2018/Hören")
      )
      (libsource (lib "chickenfood") (part "R"))
    )
    (comp (ref "R139")
      (value "10K")
      (footprint "R0402 Reflow")
      (description "RES SMD 10K OHM 1% 1/16W 0402")
      (fields
        (field (name "TOLERANCE") "±1%")
        (field (name "02. DISTRIBUTOR PART NUMBER") "311-10.0KLRDKR-ND")
        (field (name "13. CREATED DATE/NAME") "AUG2018/Hören")
      )
      (libsource (lib "chickenfood") (part "R"))
    )
    (comp (ref "R140")
      (value "DNM")
      (footprint "R0402 Reflow")
      (description "RES SMD 10K OHM 1% 1/16W 0402")
      (fields
        (field (name "TOLERANCE") "±1%")
        (field (name "02. DISTRIBUTOR PART NUMBER") "311-10.0KLRDKR-ND")
        (field (name "13. CREATED DATE/NAME") "AUG2018/Hören")
      )
      (libsource (lib "chickenfood") (part "R"))
    )
    (comp (ref "R141")
      (value "1k")
      (footprint "R0402 Reflow")
      (description "RES SMD 1K OHM 1% 1/16W 0402")
      (fields
        (field (name "TOLERANCE") "±1%")
        (field (name "02. DISTRIBUTOR PART NUMBER") "YAG1254CT-ND")
        (field (name "13. CREATED DATE/NAME") "AUG2018/Hören")
      )
      (libsource (lib "") (part "R_1"))
    )
    (comp (ref "TP6")
      (value "TP")
      (footprint "DualTestpoint 100mils")
      (description "Dual testpoint, pitch 2.54mm")
      (fields
        (field (name "02. DISTRIBUTOR PART NUMBER") "HMTSW-103-07-G-S-240")
        (field (name "13. CREATED DATE/NAME") "AUG2018/Hören")
      )
      (libsource (lib "PCB-Tester-Board-V1") (part "DualTestpoint 100mils"))
    )
    (comp (ref "TP7")
      (value "TP")
      (footprint "DualTestpoint 100mils")
      (description "Dual testpoint, pitch 2.54mm")
      (fields
        (field (name "02. DISTRIBUTOR PART NUMBER") "HMTSW-103-07-G-S-240")
        (field (name "13. CREATED DATE/NAME") "AUG2018/Hören")
      )
      (libsource (lib "PCB-Tester-Board-V1") (part "DualTestpoint 100mils"))
    )
    (comp (ref "TP8")
      (value "TP")
      (footprint "DualTestpoint 100mils")
      (description "Dual testpoint, pitch 2.54mm")
      (fields
        (field (name "02. DISTRIBUTOR PART NUMBER") "HMTSW-103-07-G-S-240")
        (field (name "13. CREATED DATE/NAME") "AUG2018/Hören")
      )
      (libsource (lib "PCB-Tester-Board-V1") (part "DualTestpoint 100mils"))
    )
    (comp (ref "TP9")
      (value "TP")
      (footprint "DualTestpoint 100mils")
      (description "Dual testpoint, pitch 2.54mm")
      (fields
        (field (name "02. DISTRIBUTOR PART NUMBER") "HMTSW-103-07-G-S-240")
        (field (name "13. CREATED DATE/NAME") "AUG2018/Hören")
      )
      (libsource (lib "PCB-Tester-Board-V1") (part "DualTestpoint 100mils"))
    )
    (comp (ref "U3")
      (value "IRPS5401M")
      (footprint "QFN4-7x7-56_IRPS5401M")
      (description "POL - SUPIRBUCK")
      (fields
        (field (name "MFR") "Infineon")
        (field (name "07. MANUFACTURER  PART NUMBER") "IRPS5401MTRPBF")
        (field (name "NICNAME") "IRPS5401M")
      )
      (libsource (lib "PCB-Tester-Board-V1") (part "IRPS5401M"))
    )
  )
  (nets
    (net (code "2") (name "/PG_A") (class "Default")
      (node (ref "Q30") (pin "1") (pinfunction "G_1") (pintype "passive"))
      (node (ref "R120") (pin "1") (pinfunction "1_1") (pintype "passive"))
      (node (ref "U3") (pin "26") (pinfunction "PG_A_26") (pintype "passive"))
    )
    (net (code "3") (name "/PG_B") (class "Default")
      (node (ref "Q78") (pin "1") (pinfunction "G_1") (pintype "passive"))
      (node (ref "R124") (pin "1") (pinfunction "1_1") (pintype "passive"))
      (node (ref "U3") (pin "30") (pinfunction "PG_B_30") (pintype "passive"))
    )
    (net (code "4") (name "/PG_C") (class "Default")
      (node (ref "Q79") (pin "1") (pinfunction "G_1") (pintype "passive"))
      (node (ref "R131") (pin "1") (pinfunction "1_1") (pintype "passive"))
      (node (ref "U3") (pin "27") (pinfunction "PG_C_27") (pintype "passive"))
    )
    (net (code "5") (name "/PG_D") (class "Default")
      (node (ref "Q80") (pin "1") (pinfunction "G_1") (pintype "passive"))
      (node (ref "R138") (pin "1") (pinfunction "1_1") (pintype "passive"))
      (node (ref "U3") (pin "16") (pinfunction "PG_D_16") (pintype "passive"))
    )
    (net (code "6") (name "/Vcc") (class "Default")
      (node (ref "C49") (pin "1") (pinfunction "1_1") (pintype "passive"))
      (node (ref "C50") (pin "1") (pinfunction "1_1") (pintype "passive"))
      (node (ref "R123") (pin "2") (pinfunction "2_2") (pintype "passive"))
      (node (ref "U3") (pin "29") (pinfunction "SLEEP#_29") (pintype "passive"))
      (node (ref "U3") (pin "48") (pinfunction "VCC_48") (pintype "passive"))
    )
    (net (code "7") (name "/Vin") (class "Default")
      (node (ref "C18") (pin "1") (pinfunction "1_1") (pintype "passive"))
      (node (ref "C19") (pin "1") (pinfunction "1_1") (pintype "passive"))
      (node (ref "C20") (pin "1") (pinfunction "1_1") (pintype "passive"))
      (node (ref "C21") (pin "1") (pinfunction "1_1") (pintype "passive"))
      (node (ref "C22") (pin "1") (pinfunction "1_1") (pintype "passive"))
      (node (ref "C23") (pin "1") (pinfunction "1_1") (pintype "passive"))
      (node (ref "C38") (pin "1") (pinfunction "1_1") (pintype "passive"))
      (node (ref "C41") (pin "1") (pinfunction "1_1") (pintype "passive"))
      (node (ref "C43") (pin "1") (pinfunction "1_1") (pintype "passive"))
      (node (ref "C44") (pin "1") (pinfunction "1_1") (pintype "passive"))
      (node (ref "C45") (pin "1") (pinfunction "1_1") (pintype "passive"))
      (node (ref "C47") (pin "1") (pinfunction "1_1") (pintype "passive"))
      (node (ref "C7") (pin "1") (pinfunction "1_1") (pintype "passive"))
      (node (ref "C8") (pin "1") (pinfunction "1_1") (pintype "passive"))
      (node (ref "U3") (pin "1") (pinfunction "VIN_D_1") (pintype "passive"))
      (node (ref "U3") (pin "12") (pinfunction "VIN_C_12") (pintype "passive"))
      (node (ref "U3") (pin "32") (pinfunction "VIN_B_32") (pintype "passive"))
      (node (ref "U3") (pin "39") (pinfunction "VIN_A_39") (pintype "passive"))
      (node (ref "U3") (pin "49") (pinfunction "VSUPPLY_49") (pintype "passive"))
    )
    (net (code "8") (name "/Vout1") (class "Default")
      (node (ref "C66") (pin "1") (pinfunction "1_1") (pintype "passive"))
      (node (ref "J5") (pin "2") (pinfunction "2_2") (pintype "passive"))
      (node (ref "J6") (pin "2") (pinfunction "2_2") (pintype "passive"))
    )
    (net (code "9") (name "/Vout2") (class "Default")
      (node (ref "C67") (pin "1") (pinfunction "1_1") (pintype "passive"))
      (node (ref "J7") (pin "2") (pinfunction "2_2") (pintype "passive"))
      (node (ref "J8") (pin "2") (pinfunction "2_2") (pintype "passive"))
    )
    (net (code "10") (name "/Vout3") (class "Default")
      (node (ref "C68") (pin "1") (pinfunction "1_1") (pintype "passive"))
      (node (ref "J10") (pin "2") (pinfunction "2_2") (pintype "passive"))
      (node (ref "J9") (pin "2") (pinfunction "2_2") (pintype "passive"))
    )
    (net (code "11") (name "/Vout4") (class "Default")
      (node (ref "C69") (pin "1") (pinfunction "1_1") (pintype "passive"))
      (node (ref "J11") (pin "2") (pinfunction "2_2") (pintype "passive"))
      (node (ref "J12") (pin "2") (pinfunction "2_2") (pintype "passive"))
    )
    (net (code "12") (name "/nPOR_F") (class "Default")
      (node (ref "Q98") (pin "3") (pinfunction "D_3") (pintype "passive"))
    )
    (net (code "14") (name "5V0") (class "Default")
      (node (ref "D10") (pin "1") (pinfunction "Anode_1") (pintype "passive"))
      (node (ref "D11") (pin "1") (pinfunction "Anode_1") (pintype "passive"))
      (node (ref "D12") (pin "1") (pinfunction "Anode_1") (pintype "passive"))
      (node (ref "D9") (pin "1") (pinfunction "Anode_1") (pintype "passive"))
      (node (ref "R120") (pin "2") (pinfunction "2_2") (pintype "passive"))
      (node (ref "R121") (pin "2") (pinfunction "2_2") (pintype "passive"))
      (node (ref "R124") (pin "2") (pinfunction "2_2") (pintype "passive"))
      (node (ref "R125") (pin "2") (pinfunction "2_2") (pintype "passive"))
      (node (ref "R131") (pin "2") (pinfunction "2_2") (pintype "passive"))
      (node (ref "R132") (pin "2") (pinfunction "2_2") (pintype "passive"))
      (node (ref "R138") (pin "2") (pinfunction "2_2") (pintype "passive"))
      (node (ref "R139") (pin "2") (pinfunction "2_2") (pintype "passive"))
    )
    (net (code "15") (name "GND") (class "Default")
      (node (ref "C18") (pin "2") (pinfunction "2_2") (pintype "passive"))
      (node (ref "C19") (pin "2") (pinfunction "2_2") (pintype "passive"))
      (node (ref "C20") (pin "2") (pinfunction "2_2") (pintype "passive"))
      (node (ref "C21") (pin "2") (pinfunction "2_2") (pintype "passive"))
      (node (ref "C22") (pin "2") (pinfunction "2_2") (pintype "passive"))
      (node (ref "C23") (pin "2") (pinfunction "2_2") (pintype "passive"))
      (node (ref "C24") (pin "2") (pinfunction "2_2") (pintype "passive"))
      (node (ref "C25") (pin "2") (pinfunction "2_2") (pintype "passive"))
      (node (ref "C26") (pin "2") (pinfunction "2_2") (pintype "passive"))
      (node (ref "C27") (pin "2") (pinfunction "2_2") (pintype "passive"))
      (node (ref "C28") (pin "2") (pinfunction "2_2") (pintype "passive"))
      (node (ref "C29") (pin "2") (pinfunction "2_2") (pintype "passive"))
      (node (ref "C30") (pin "2") (pinfunction "2_2") (pintype "passive"))
      (node (ref "C31") (pin "2") (pinfunction "2_2") (pintype "passive"))
      (node (ref "C32") (pin "2") (pinfunction "2_2") (pintype "passive"))
      (node (ref "C33") (pin "2") (pinfunction "2_2") (pintype "passive"))
      (node (ref "C34") (pin "2") (pinfunction "2_2") (pintype "passive"))
      (node (ref "C35") (pin "2") (pinfunction "2_2") (pintype "passive"))
      (node (ref "C38") (pin "2") (pinfunction "2_2") (pintype "passive"))
      (node (ref "C41") (pin "2") (pinfunction "2_2") (pintype "passive"))
      (node (ref "C42") (pin "2") (pinfunction "2_2") (pintype "passive"))
      (node (ref "C43") (pin "2") (pinfunction "2_2") (pintype "passive"))
      (node (ref "C44") (pin "2") (pinfunction "2_2") (pintype "passive"))
      (node (ref "C45") (pin "2") (pinfunction "2_2") (pintype "passive"))
      (node (ref "C47") (pin "2") (pinfunction "2_2") (pintype "passive"))
      (node (ref "C48") (pin "2") (pinfunction "2_2") (pintype "passive"))
      (node (ref "C49") (pin "2") (pinfunction "2_2") (pintype "passive"))
      (node (ref "C50") (pin "2") (pinfunction "2_2") (pintype "passive"))
      (node (ref "C51") (pin "2") (pinfunction "2_2") (pintype "passive"))
      (node (ref "C52") (pin "2") (pinfunction "2_2") (pintype "passive"))
      (node (ref "C53") (pin "2") (pinfunction "2_2") (pintype "passive"))
      (node (ref "C54") (pin "2") (pinfunction "2_2") (pintype "passive"))
      (node (ref "C56") (pin "2") (pinfunction "2_2") (pintype "passive"))
      (node (ref "C58") (pin "2") (pinfunction "2_2") (pintype "passive"))
      (node (ref "C59") (pin "2") (pinfunction "2_2") (pintype "passive"))
      (node (ref "C60") (pin "2") (pinfunction "2_2") (pintype "passive"))
      (node (ref "C66") (pin "2") (pinfunction "2_2") (pintype "passive"))
      (node (ref "C67") (pin "2") (pinfunction "2_2") (pintype "passive"))
      (node (ref "C68") (pin "2") (pinfunction "2_2") (pintype "passive"))
      (node (ref "C69") (pin "2") (pinfunction "2_2") (pintype "passive"))
      (node (ref "C7") (pin "2") (pinfunction "2_2") (pintype "passive"))
      (node (ref "C8") (pin "2") (pinfunction "2_2") (pintype "passive"))
      (node (ref "Q30") (pin "2") (pinfunction "S_2") (pintype "passive"))
      (node (ref "Q78") (pin "2") (pinfunction "S_2") (pintype "passive"))
      (node (ref "Q79") (pin "2") (pinfunction "S_2") (pintype "passive"))
      (node (ref "Q80") (pin "2") (pinfunction "S_2") (pintype "passive"))
      (node (ref "Q98") (pin "2") (pinfunction "S_2") (pintype "passive"))
      (node (ref "R122") (pin "2") (pinfunction "2_2") (pintype "passive"))
      (node (ref "R126") (pin "2") (pinfunction "2_2") (pintype "passive"))
      (node (ref "R133") (pin "2") (pinfunction "2_2") (pintype "passive"))
      (node (ref "R134") (pin "1") (pinfunction "1_1") (pintype "passive"))
      (node (ref "R136") (pin "1") (pinfunction "1_1") (pintype "passive"))
      (node (ref "R137") (pin "1") (pinfunction "1_1") (pintype "passive"))
      (node (ref "R140") (pin "2") (pinfunction "2_2") (pintype "passive"))
      (node (ref "R141") (pin "1") (pinfunction "1_1") (pintype "passive"))
      (node (ref "R95") (pin "1") (pinfunction "1_1") (pintype "passive"))
      (node (ref "R97") (pin "1") (pinfunction "1_1") (pintype "passive"))
      (node (ref "TP6") (pin "2") (pinfunction "2_2") (pintype "passive"))
      (node (ref "TP7") (pin "2") (pinfunction "2_2") (pintype "passive"))
      (node (ref "TP8") (pin "2") (pinfunction "2_2") (pintype "passive"))
      (node (ref "TP9") (pin "2") (pinfunction "2_2") (pintype "passive"))
      (node (ref "U3") (pin "22") (pinfunction "VIN_LDO_22") (pintype "passive"))
      (node (ref "U3") (pin "28") (pinfunction "EN_L_28") (pintype "passive"))
      (node (ref "U3") (pin "40") (pinfunction "RTN_A_40") (pintype "passive"))
      (node (ref "U3") (pin "50") (pinfunction "AGND_50") (pintype "passive"))
      (node (ref "U3") (pin "52") (pinfunction "SYNC_CLK_52") (pintype "passive"))
      (node (ref "U3") (pin "57") (pinfunction "GND_57") (pintype "passive"))
    )
    (net (code "16") (name "Net-(C24-Pad1)") (class "Default")
      (node (ref "C24") (pin "1") (pinfunction "1_1") (pintype "passive"))
      (node (ref "C25") (pin "1") (pinfunction "1_1") (pintype "passive"))
      (node (ref "C26") (pin "1") (pinfunction "1_1") (pintype "passive"))
      (node (ref "C42") (pin "1") (pinfunction "1_1") (pintype "passive"))
      (node (ref "J5") (pin "1") (pinfunction "1_1") (pintype "passive"))
      (node (ref "J6") (pin "1") (pinfunction "1_1") (pintype "passive"))
      (node (ref "L3") (pin "2") (pinfunction "2_2") (pintype "passive"))
      (node (ref "R94") (pin "2") (pinfunction "2_2") (pintype "passive"))
      (node (ref "TP6") (pin "1") (pinfunction "1_1") (pintype "passive"))
    )
    (net (code "17") (name "Net-(C27-Pad1)") (class "Default")
      (node (ref "C27") (pin "1") (pinfunction "1_1") (pintype "passive"))
      (node (ref "C28") (pin "1") (pinfunction "1_1") (pintype "passive"))
      (node (ref "C29") (pin "1") (pinfunction "1_1") (pintype "passive"))
      (node (ref "C48") (pin "1") (pinfunction "1_1") (pintype "passive"))
      (node (ref "J7") (pin "1") (pinfunction "1_1") (pintype "passive"))
      (node (ref "J8") (pin "1") (pinfunction "1_1") (pintype "passive"))
      (node (ref "L4") (pin "2") (pinfunction "2_2") (pintype "passive"))
      (node (ref "R96") (pin "2") (pinfunction "2_2") (pintype "passive"))
      (node (ref "TP7") (pin "1") (pinfunction "1_1") (pintype "passive"))
    )
    (net (code "18") (name "Net-(C30-Pad1)") (class "Default")
      (node (ref "C30") (pin "1") (pinfunction "1_1") (pintype "passive"))
      (node (ref "C31") (pin "1") (pinfunction "1_1") (pintype "passive"))
      (node (ref "C32") (pin "1") (pinfunction "1_1") (pintype "passive"))
      (node (ref "C56") (pin "1") (pinfunction "1_1") (pintype "passive"))
      (node (ref "J10") (pin "1") (pinfunction "1_1") (pintype "passive"))
      (node (ref "J9") (pin "1") (pinfunction "1_1") (pintype "passive"))
      (node (ref "L5") (pin "2") (pinfunction "2_2") (pintype "passive"))
      (node (ref "R130") (pin "2") (pinfunction "2_2") (pintype "passive"))
      (node (ref "TP8") (pin "1") (pinfunction "1_1") (pintype "passive"))
    )
    (net (code "19") (name "Net-(C33-Pad1)") (class "Default")
      (node (ref "C33") (pin "1") (pinfunction "1_1") (pintype "passive"))
      (node (ref "C34") (pin "1") (pinfunction "1_1") (pintype "passive"))
      (node (ref "C35") (pin "1") (pinfunction "1_1") (pintype "passive"))
      (node (ref "C60") (pin "1") (pinfunction "1_1") (pintype "passive"))
      (node (ref "J11") (pin "1") (pinfunction "1_1") (pintype "passive"))
      (node (ref "J12") (pin "1") (pinfunction "1_1") (pintype "passive"))
      (node (ref "L6") (pin "2") (pinfunction "2_2") (pintype "passive"))
      (node (ref "R135") (pin "2") (pinfunction "2_2") (pintype "passive"))
      (node (ref "TP9") (pin "1") (pinfunction "1_1") (pintype "passive"))
    )
    (net (code "20") (name "Net-(D9-Cathode)") (class "Default")
      (node (ref "D9") (pin "2") (pinfunction "Cathode_2") (pintype "passive"))
      (node (ref "R99") (pin "2") (pinfunction "2_2") (pintype "passive"))
    )
    (net (code "21") (name "Net-(D10-Cathode)") (class "Default")
      (node (ref "D10") (pin "2") (pinfunction "Cathode_2") (pintype "passive"))
      (node (ref "R101") (pin "2") (pinfunction "2_2") (pintype "passive"))
    )
    (net (code "22") (name "Net-(D11-Cathode)") (class "Default")
      (node (ref "D11") (pin "2") (pinfunction "Cathode_2") (pintype "passive"))
      (node (ref "R103") (pin "2") (pinfunction "2_2") (pintype "passive"))
    )
    (net (code "23") (name "Net-(D12-Cathode)") (class "Default")
      (node (ref "D12") (pin "2") (pinfunction "Cathode_2") (pintype "passive"))
      (node (ref "R105") (pin "2") (pinfunction "2_2") (pintype "passive"))
    )
    (net (code "24") (name "Net-(Q30-D)") (class "Default")
      (node (ref "Q30") (pin "3") (pinfunction "D_3") (pintype "passive"))
      (node (ref "R99") (pin "1") (pinfunction "1_1") (pintype "passive"))
    )
    (net (code "25") (name "Net-(Q78-D)") (class "Default")
      (node (ref "Q78") (pin "3") (pinfunction "D_3") (pintype "passive"))
      (node (ref "R101") (pin "1") (pinfunction "1_1") (pintype "passive"))
    )
    (net (code "26") (name "Net-(Q79-D)") (class "Default")
      (node (ref "Q79") (pin "3") (pinfunction "D_3") (pintype "passive"))
      (node (ref "R103") (pin "1") (pinfunction "1_1") (pintype "passive"))
    )
    (net (code "27") (name "Net-(Q80-D)") (class "Default")
      (node (ref "Q80") (pin "3") (pinfunction "D_3") (pintype "passive"))
      (node (ref "Q98") (pin "1") (pinfunction "G_1") (pintype "passive"))
      (node (ref "R105") (pin "1") (pinfunction "1_1") (pintype "passive"))
    )
    (net (code "28") (name "Net-(U3A-BOOT_A)") (class "Default")
      (node (ref "C40") (pin "1") (pinfunction "1_1") (pintype "passive"))
      (node (ref "U3") (pin "38") (pinfunction "BOOT_A_38") (pintype "passive"))
    )
    (net (code "29") (name "Net-(U3A-EN_A)") (class "Default")
      (node (ref "R121") (pin "1") (pinfunction "1_1") (pintype "passive"))
      (node (ref "R122") (pin "1") (pinfunction "1_1") (pintype "passive"))
      (node (ref "U3") (pin "42") (pinfunction "EN_A_42") (pintype "passive"))
    )
    (net (code "30") (name "Net-(U3A-FB_A)") (class "Default")
      (node (ref "R94") (pin "1") (pinfunction "1_1") (pintype "passive"))
      (node (ref "R95") (pin "2") (pinfunction "2_2") (pintype "passive"))
      (node (ref "U3") (pin "41") (pinfunction "FB_A_41") (pintype "passive"))
    )
    (net (code "31") (name "Net-(U3A-ISEN_A+)") (class "Default")
      (node (ref "U3") (pin "45") (pinfunction "ISEN_A-_45") (pintype "passive"))
      (node (ref "U3") (pin "46") (pinfunction "ISEN_A+_46") (pintype "passive"))
    )
    (net (code "32") (name "Net-(U3A-PHASE_A)") (class "Default")
      (node (ref "C40") (pin "2") (pinfunction "2_2") (pintype "passive"))
      (node (ref "L3") (pin "1") (pinfunction "1_1") (pintype "passive"))
      (node (ref "U3") (pin "36") (pinfunction "PHASE_A_36") (pintype "passive"))
    )
    (net (code "33") (name "Net-(U3B-BOOT_B)") (class "Default")
      (node (ref "C46") (pin "1") (pinfunction "1_1") (pintype "passive"))
      (node (ref "U3") (pin "33") (pinfunction "BOOT_B_33") (pintype "passive"))
    )
    (net (code "34") (name "Net-(U3B-EN_B)") (class "Default")
      (node (ref "R125") (pin "1") (pinfunction "1_1") (pintype "passive"))
      (node (ref "R126") (pin "1") (pinfunction "1_1") (pintype "passive"))
      (node (ref "U3") (pin "44") (pinfunction "EN_B_44") (pintype "passive"))
    )
    (net (code "35") (name "Net-(U3B-FB_B)") (class "Default")
      (node (ref "R96") (pin "1") (pinfunction "1_1") (pintype "passive"))
      (node (ref "R97") (pin "2") (pinfunction "2_2") (pintype "passive"))
      (node (ref "U3") (pin "31") (pinfunction "FB_B_31") (pintype "passive"))
    )
    (net (code "36") (name "Net-(U3B-PHASE_B)") (class "Default")
      (node (ref "C46") (pin "2") (pinfunction "2_2") (pintype "passive"))
      (node (ref "L4") (pin "1") (pinfunction "1_1") (pintype "passive"))
      (node (ref "U3") (pin "34") (pinfunction "PHASE_B_34") (pintype "passive"))
    )
    (net (code "37") (name "Net-(U3C-BOOT_C)") (class "Default")
      (node (ref "C55") (pin "1") (pinfunction "1_1") (pintype "passive"))
      (node (ref "U3") (pin "11") (pinfunction "BOOT_C_11") (pintype "passive"))
    )
    (net (code "38") (name "Net-(U3C-EN_C)") (class "Default")
      (node (ref "R132") (pin "1") (pinfunction "1_1") (pintype "passive"))
      (node (ref "R133") (pin "1") (pinfunction "1_1") (pintype "passive"))
      (node (ref "U3") (pin "51") (pinfunction "EN_C_51") (pintype "passive"))
    )
    (net (code "39") (name "Net-(U3C-FB_C)") (class "Default")
      (node (ref "R130") (pin "1") (pinfunction "1_1") (pintype "passive"))
      (node (ref "R134") (pin "2") (pinfunction "2_2") (pintype "passive"))
      (node (ref "U3") (pin "15") (pinfunction "FB_C_15") (pintype "passive"))
    )
    (net (code "40") (name "Net-(U3C-PHASE_C)") (class "Default")
      (node (ref "C55") (pin "2") (pinfunction "2_2") (pintype "passive"))
      (node (ref "L5") (pin "1") (pinfunction "1_1") (pintype "passive"))
      (node (ref "U3") (pin "8") (pinfunction "PHASE_C_8") (pintype "passive"))
    )
    (net (code "41") (name "Net-(U3D-BOOT_D)") (class "Default")
      (node (ref "C57") (pin "1") (pinfunction "1_1") (pintype "passive"))
      (node (ref "U3") (pin "4") (pinfunction "BOOT_D_4") (pintype "passive"))
    )
    (net (code "42") (name "Net-(U3D-EN_D)") (class "Default")
      (node (ref "R139") (pin "1") (pinfunction "1_1") (pintype "passive"))
      (node (ref "R140") (pin "1") (pinfunction "1_1") (pintype "passive"))
      (node (ref "U3") (pin "53") (pinfunction "EN_D_53") (pintype "passive"))
    )
    (net (code "43") (name "Net-(U3D-FB_D)") (class "Default")
      (node (ref "R135") (pin "1") (pinfunction "1_1") (pintype "passive"))
      (node (ref "R141") (pin "2") (pinfunction "2_2") (pintype "passive"))
      (node (ref "U3") (pin "56") (pinfunction "FB_D_56") (pintype "passive"))
    )
    (net (code "44") (name "Net-(U3D-PHASE_D)") (class "Default")
      (node (ref "C57") (pin "2") (pinfunction "2_2") (pintype "passive"))
      (node (ref "L6") (pin "1") (pinfunction "1_1") (pintype "passive"))
      (node (ref "U3") (pin "5") (pinfunction "PHASE_D_5") (pintype "passive"))
    )
    (net (code "45") (name "Net-(U3E-1V8)") (class "Default")
      (node (ref "C54") (pin "1") (pinfunction "1_1") (pintype "passive"))
      (node (ref "U3") (pin "21") (pinfunction "1V8_21") (pintype "passive"))
    )
    (net (code "46") (name "Net-(U3E-ADDR_PROT)") (class "Default")
      (node (ref "C59") (pin "1") (pinfunction "1_1") (pintype "passive"))
      (node (ref "R137") (pin "2") (pinfunction "2_2") (pintype "passive"))
      (node (ref "U3") (pin "55") (pinfunction "ADDR_PROT_55") (pintype "passive"))
    )
    (net (code "47") (name "Net-(U3E-ALERT#)") (class "Default")
      (node (ref "R127") (pin "1") (pinfunction "1_1") (pintype "passive"))
      (node (ref "U3") (pin "17") (pinfunction "ALERT#_17") (pintype "passive"))
    )
    (net (code "48") (name "Net-(U3E-CLK)") (class "Default")
      (node (ref "R128") (pin "1") (pinfunction "1_1") (pintype "passive"))
      (node (ref "U3") (pin "18") (pinfunction "CLK_18") (pintype "passive"))
    )
    (net (code "49") (name "Net-(U3E-DATA)") (class "Default")
      (node (ref "R129") (pin "1") (pinfunction "1_1") (pintype "passive"))
      (node (ref "U3") (pin "19") (pinfunction "DATA_19") (pintype "passive"))
    )
    (net (code "50") (name "Net-(U3E-MTP)") (class "Default")
      (node (ref "C58") (pin "1") (pinfunction "1_1") (pintype "passive"))
      (node (ref "R136") (pin "2") (pinfunction "2_2") (pintype "passive"))
      (node (ref "U3") (pin "54") (pinfunction "MTP_54") (pintype "passive"))
    )
    (net (code "51") (name "Net-(U3E-VDDIO)") (class "Default")
      (node (ref "C53") (pin "1") (pinfunction "1_1") (pintype "passive"))
      (node (ref "R127") (pin "2") (pinfunction "2_2") (pintype "passive"))
      (node (ref "R128") (pin "2") (pinfunction "2_2") (pintype "passive"))
      (node (ref "R129") (pin "2") (pinfunction "2_2") (pintype "passive"))
      (node (ref "U3") (pin "20") (pinfunction "VDDIO_20") (pintype "passive"))
    )
    (net (code "52") (name "Net-(U3E-VDRV)") (class "Default")
      (node (ref "C51") (pin "1") (pinfunction "1_1") (pintype "passive"))
      (node (ref "C52") (pin "1") (pinfunction "1_1") (pintype "passive"))
      (node (ref "R123") (pin "1") (pinfunction "1_1") (pintype "passive"))
      (node (ref "U3") (pin "47") (pinfunction "VDRV_47") (pintype "passive"))
    )
    (net (code "53") (name "unconnected-(U3A-PWM_A-Pad43)") (class "Default")
      (node (ref "U3") (pin "43") (pinfunction "PWM_A_43") (pintype "passive+no_connect"))
    )
    (net (code "54") (name "unconnected-(U3E-FB_L-Pad24)") (class "Default")
      (node (ref "U3") (pin "24") (pinfunction "FB_L_24") (pintype "passive+no_connect"))
    )
    (net (code "55") (name "unconnected-(U3E-PG_L-Pad25)") (class "Default")
      (node (ref "U3") (pin "25") (pinfunction "PG_L_25") (pintype "passive+no_connect"))
    )
    (net (code "56") (name "unconnected-(U3E-VO_LDO-Pad23)") (class "Default")
      (node (ref "U3") (pin "23") (pinfunction "VO_LDO_23") (pintype "passive+no_connect"))
    )
  )
)
